# hhv-dcdarknet-varient-4.net
KiCad netlist of a schematic drawn in EAGLE
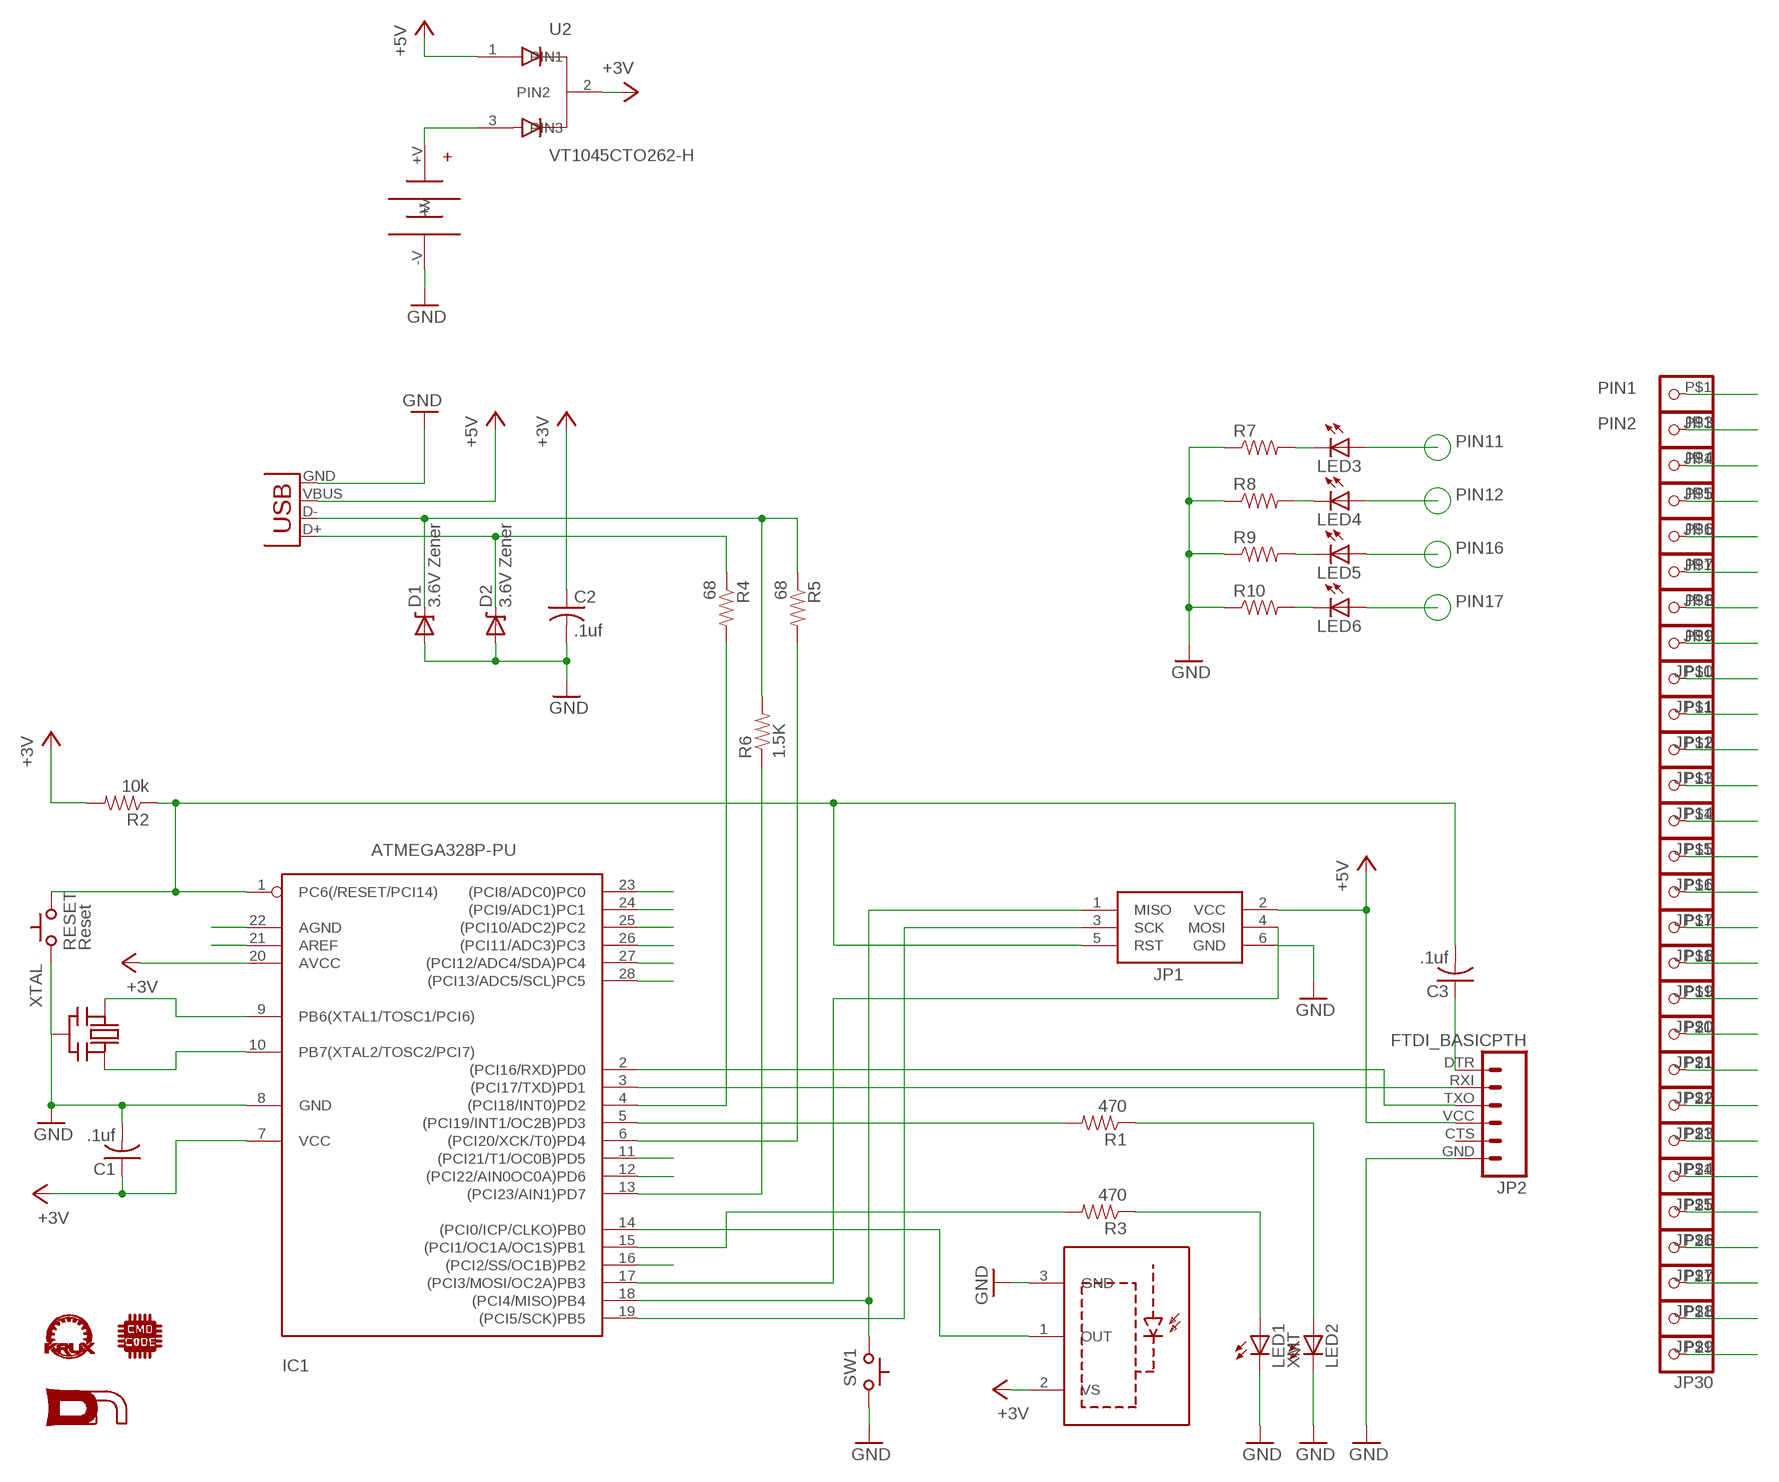
[diagram p0: schematic, sheet 1]

(export (version "E")
  (design (tool "Eeschema 10.0.6"))
  (components
    (comp (ref "C1")
      (value ".1uf")
      (footprint "eagle-import:C025-030X050")
      (libsource (lib "eagle-import") (part "C-US025-030X050"))
    )
    (comp (ref "C2")
      (value ".1uf")
      (footprint "eagle-import:C025-030X050")
      (libsource (lib "eagle-import") (part "C-US025-030X050"))
    )
    (comp (ref "C3")
      (value ".1uf")
      (footprint "eagle-import:C025-030X050")
      (libsource (lib "eagle-import") (part "C-US025-030X050"))
    )
    (comp (ref "D1")
      (value "3.6V Zener")
      (footprint "eagle-import:DIODE-ZENER")
      (libsource (lib "eagle-import") (part "DIODE-ZENERPTH"))
    )
    (comp (ref "D2")
      (value "3.6V Zener")
      (footprint "eagle-import:DIODE-ZENER")
      (libsource (lib "eagle-import") (part "DIODE-ZENERPTH"))
    )
    (comp (ref "IC1")
      (value "ATMEGA328P-PU")
      (footprint "eagle-import:DIL28-3")
      (libsource (lib "eagle-import") (part "ATMEGA168PV-10"))
    )
    (comp (ref "JP1")
      (value "JP1")
      (footprint "eagle-import:AVRISP")
      (libsource (lib "eagle-import") (part "AVRISP-6"))
    )
    (comp (ref "JP2")
      (value "FTDI_BASICPTH")
      (footprint "eagle-import:FTDI_BASIC")
      (libsource (lib "eagle-import") (part "FTDI_BASICPTH"))
    )
    (comp (ref "JP3")
      (value "PINHD-1X11X1_SQUARE")
      (footprint "eagle-import:1X1-SMALL_CUT")
      (libsource (lib "eagle-import") (part "PINHD-1X11X1_SQUARE"))
    )
    (comp (ref "JP4")
      (value "PINHD-1X11X1_SQUARE")
      (footprint "eagle-import:1X1-SMALL_CUT")
      (libsource (lib "eagle-import") (part "PINHD-1X11X1_SQUARE"))
    )
    (comp (ref "JP5")
      (value "PINHD-1X11X1_SQUARE")
      (footprint "eagle-import:1X1-SMALL_CUT")
      (libsource (lib "eagle-import") (part "PINHD-1X11X1_SQUARE"))
    )
    (comp (ref "JP6")
      (value "PINHD-1X11X1_SQUARE")
      (footprint "eagle-import:1X1-SMALL_CUT")
      (libsource (lib "eagle-import") (part "PINHD-1X11X1_SQUARE"))
    )
    (comp (ref "JP7")
      (value "PINHD-1X11X1_SQUARE")
      (footprint "eagle-import:1X1-SMALL_CUT")
      (libsource (lib "eagle-import") (part "PINHD-1X11X1_SQUARE"))
    )
    (comp (ref "JP8")
      (value "PINHD-1X11X1_SQUARE")
      (footprint "eagle-import:1X1-SMALL_CUT")
      (libsource (lib "eagle-import") (part "PINHD-1X11X1_SQUARE"))
    )
    (comp (ref "JP9")
      (value "PINHD-1X11X1_SQUARE")
      (footprint "eagle-import:1X1-SMALL_CUT")
      (libsource (lib "eagle-import") (part "PINHD-1X11X1_SQUARE"))
    )
    (comp (ref "JP10")
      (value "PINHD-1X11X1_SQUARE")
      (footprint "eagle-import:1X1-SMALL_CUT")
      (libsource (lib "eagle-import") (part "PINHD-1X11X1_SQUARE"))
    )
    (comp (ref "JP11")
      (value "PINHD-1X11X1_SQUARE")
      (footprint "eagle-import:1X1-SMALL_CUT")
      (libsource (lib "eagle-import") (part "PINHD-1X11X1_SQUARE"))
    )
    (comp (ref "JP12")
      (value "PINHD-1X11X1_SQUARE")
      (footprint "eagle-import:1X1-SMALL_CUT")
      (libsource (lib "eagle-import") (part "PINHD-1X11X1_SQUARE"))
    )
    (comp (ref "JP13")
      (value "PINHD-1X11X1_SQUARE")
      (footprint "eagle-import:1X1-SMALL_CUT")
      (libsource (lib "eagle-import") (part "PINHD-1X11X1_SQUARE"))
    )
    (comp (ref "JP14")
      (value "PINHD-1X11X1_SQUARE")
      (footprint "eagle-import:1X1-SMALL_CUT")
      (libsource (lib "eagle-import") (part "PINHD-1X11X1_SQUARE"))
    )
    (comp (ref "JP15")
      (value "PINHD-1X11X1_SQUARE")
      (footprint "eagle-import:1X1-SMALL_CUT")
      (libsource (lib "eagle-import") (part "PINHD-1X11X1_SQUARE"))
    )
    (comp (ref "JP16")
      (value "PINHD-1X11X1_SQUARE")
      (footprint "eagle-import:1X1-SMALL_CUT")
      (libsource (lib "eagle-import") (part "PINHD-1X11X1_SQUARE"))
    )
    (comp (ref "JP17")
      (value "PINHD-1X11X1_SQUARE")
      (footprint "eagle-import:1X1-SMALL_CUT")
      (libsource (lib "eagle-import") (part "PINHD-1X11X1_SQUARE"))
    )
    (comp (ref "JP18")
      (value "PINHD-1X11X1_SQUARE")
      (footprint "eagle-import:1X1-SMALL_CUT")
      (libsource (lib "eagle-import") (part "PINHD-1X11X1_SQUARE"))
    )
    (comp (ref "JP19")
      (value "PINHD-1X11X1_SQUARE")
      (footprint "eagle-import:1X1-SMALL_CUT")
      (libsource (lib "eagle-import") (part "PINHD-1X11X1_SQUARE"))
    )
    (comp (ref "JP20")
      (value "PINHD-1X11X1_SQUARE")
      (footprint "eagle-import:1X1-SMALL_CUT")
      (libsource (lib "eagle-import") (part "PINHD-1X11X1_SQUARE"))
    )
    (comp (ref "JP21")
      (value "PINHD-1X11X1_SQUARE")
      (footprint "eagle-import:1X1-SMALL_CUT")
      (libsource (lib "eagle-import") (part "PINHD-1X11X1_SQUARE"))
    )
    (comp (ref "JP22")
      (value "PINHD-1X11X1_SQUARE")
      (footprint "eagle-import:1X1-SMALL_CUT")
      (libsource (lib "eagle-import") (part "PINHD-1X11X1_SQUARE"))
    )
    (comp (ref "JP23")
      (value "PINHD-1X11X1_SQUARE")
      (footprint "eagle-import:1X1-SMALL_CUT")
      (libsource (lib "eagle-import") (part "PINHD-1X11X1_SQUARE"))
    )
    (comp (ref "JP24")
      (value "PINHD-1X11X1_SQUARE")
      (footprint "eagle-import:1X1-SMALL_CUT")
      (libsource (lib "eagle-import") (part "PINHD-1X11X1_SQUARE"))
    )
    (comp (ref "JP25")
      (value "PINHD-1X11X1_SQUARE")
      (footprint "eagle-import:1X1-SMALL_CUT")
      (libsource (lib "eagle-import") (part "PINHD-1X11X1_SQUARE"))
    )
    (comp (ref "JP26")
      (value "PINHD-1X11X1-SMALL")
      (footprint "eagle-import:1X1-SMALL")
      (libsource (lib "eagle-import") (part "PINHD-1X11X1-SMALL"))
    )
    (comp (ref "JP27")
      (value "PINHD-1X11X1_SQUARE")
      (footprint "eagle-import:1X1-SMALL_CUT")
      (libsource (lib "eagle-import") (part "PINHD-1X11X1_SQUARE"))
    )
    (comp (ref "JP28")
      (value "PINHD-1X11X1_SQUARE")
      (footprint "eagle-import:1X1-SMALL_CUT")
      (libsource (lib "eagle-import") (part "PINHD-1X11X1_SQUARE"))
    )
    (comp (ref "JP29")
      (value "PINHD-1X11X1_SQUARE")
      (footprint "eagle-import:1X1-SMALL_CUT")
      (libsource (lib "eagle-import") (part "PINHD-1X11X1_SQUARE"))
    )
    (comp (ref "JP30")
      (value "PINHD-1X11X1-SMALL")
      (footprint "eagle-import:1X1-SMALL")
      (libsource (lib "eagle-import") (part "PINHD-1X11X1-SMALL"))
    )
    (comp (ref "LED1")
      (value "XMT")
      (footprint "eagle-import:LED5MM-FLAT")
      (libsource (lib "eagle-import") (part "LED5MM-FLAT"))
    )
    (comp (ref "LED2")
      (value "LED5MM-FLAT")
      (footprint "eagle-import:LED5MM-FLAT")
      (libsource (lib "eagle-import") (part "LED5MM-FLAT"))
    )
    (comp (ref "LED3")
      (value "LED1206")
      (footprint "eagle-import:LED-1206")
      (libsource (lib "eagle-import") (part "SparkFun_LED1206"))
    )
    (comp (ref "LED4")
      (value "LED1206")
      (footprint "eagle-import:LED-1206")
      (libsource (lib "eagle-import") (part "SparkFun_LED1206"))
    )
    (comp (ref "LED5")
      (value "LED1206")
      (footprint "eagle-import:LED-1206")
      (libsource (lib "eagle-import") (part "SparkFun_LED1206"))
    )
    (comp (ref "LED6")
      (value "LED1206")
      (footprint "eagle-import:LED-1206")
      (libsource (lib "eagle-import") (part "SparkFun_LED1206"))
    )
    (comp (ref "R1")
      (value "470")
      (footprint "eagle-import:AXIAL-0.3")
      (libsource (lib "eagle-import") (part "RESISTORAXIAL-0.3"))
    )
    (comp (ref "R2")
      (value "10k")
      (footprint "eagle-import:AXIAL-0.3")
      (libsource (lib "eagle-import") (part "RESISTORAXIAL-0.3"))
    )
    (comp (ref "R3")
      (value "470")
      (footprint "eagle-import:AXIAL-0.3")
      (libsource (lib "eagle-import") (part "RESISTORAXIAL-0.3"))
    )
    (comp (ref "R4")
      (value "68")
      (footprint "eagle-import:AXIAL-0.3")
      (libsource (lib "eagle-import") (part "RESISTORAXIAL-0.3"))
    )
    (comp (ref "R5")
      (value "68")
      (footprint "eagle-import:AXIAL-0.3")
      (libsource (lib "eagle-import") (part "RESISTORAXIAL-0.3"))
    )
    (comp (ref "R6")
      (value "1.5K")
      (footprint "eagle-import:AXIAL-0.3")
      (libsource (lib "eagle-import") (part "RESISTORAXIAL-0.3"))
    )
    (comp (ref "R7")
      (value "RESISTOR1206")
      (footprint "eagle-import:1206")
      (libsource (lib "eagle-import") (part "SparkFun_RESISTOR1206"))
    )
    (comp (ref "R8")
      (value "RESISTOR1206")
      (footprint "eagle-import:1206")
      (libsource (lib "eagle-import") (part "SparkFun_RESISTOR1206"))
    )
    (comp (ref "R9")
      (value "RESISTOR1206")
      (footprint "eagle-import:1206")
      (libsource (lib "eagle-import") (part "SparkFun_RESISTOR1206"))
    )
    (comp (ref "R10")
      (value "RESISTOR1206")
      (footprint "eagle-import:1206")
      (libsource (lib "eagle-import") (part "SparkFun_RESISTOR1206"))
    )
    (comp (ref "RESET")
      (value "Reset")
      (footprint "eagle-import:TACTILE-2PIN")
      (libsource (lib "eagle-import") (part "SWITCH_TACTILETACTILE-2PIN"))
    )
    (comp (ref "SW1")
      (value "SWITCH_TACTILETACTILE-2PIN")
      (footprint "eagle-import:TACTILE-2PIN")
      (libsource (lib "eagle-import") (part "SWITCH_TACTILETACTILE-2PIN"))
    )
    (comp (ref "U$1")
      (value "DN_LOGO")
      (footprint "eagle-import:DN_LOGO")
      (libsource (lib "eagle-import") (part "DN_LOGO"))
    )
    (comp (ref "U$2")
      (value "CMDC0DE_LOGO")
      (footprint "eagle-import:CMDC0DE")
      (libsource (lib "eagle-import") (part "CMDC0DE_LOGO"))
    )
    (comp (ref "U$3")
      (value "KRUX_LOGO")
      (footprint "eagle-import:KRUX_LOGO")
      (libsource (lib "eagle-import") (part "KRUX_LOGO"))
    )
    (comp (ref "U$5")
      (value "12BH423-GR3-CELL_NOBORDER")
      (footprint "eagle-import:3-AAA-CELL_NOBORDER")
      (libsource (lib "eagle-import") (part "12BH423-GR3-CELL_NOBORDER"))
    )
    (comp (ref "U1")
      (value "RCV")
      (footprint "eagle-import:IR-MODULE")
      (libsource (lib "eagle-import") (part "SOP22"))
    )
    (comp (ref "U2")
      (value "VT1045CTO262-H")
      (footprint "eagle-import:TO262-H")
      (libsource (lib "eagle-import") (part "VT1045CTO262-H"))
    )
    (comp (ref "X2")
      (value "USB")
      (footprint "eagle-import:USB-B-PTH")
      (libsource (lib "eagle-import") (part "USBPTH"))
    )
    (comp (ref "XTAL")
      (value "CERMOSCILL-THM")
      (footprint "eagle-import:CERM_OSC")
      (libsource (lib "eagle-import") (part "CERMOSCILL-THM"))
    )
  )
  (nets
    (net (code "1") (name "+3V") (class "Default")
      (node (ref "C1") (pin "1") (pinfunction "1_1") (pintype "passive"))
      (node (ref "C2") (pin "1") (pinfunction "1_1") (pintype "passive"))
      (node (ref "IC1") (pin "20") (pinfunction "AVCC_20") (pintype "bidirectional"))
      (node (ref "IC1") (pin "7") (pinfunction "VCC_7") (pintype "bidirectional"))
      (node (ref "JP22") (pin "P$1") (pinfunction "1_P$1") (pintype "passive"))
      (node (ref "JP9") (pin "P$1") (pinfunction "1_P$1") (pintype "passive"))
      (node (ref "R2") (pin "P$2") (pinfunction "2_P$2") (pintype "passive"))
      (node (ref "U1") (pin "2") (pinfunction "VS_2") (pintype "bidirectional"))
      (node (ref "U2") (pin "2") (pinfunction "PIN2_2") (pintype "bidirectional"))
    )
    (net (code "2") (name "+5V") (class "Default")
      (node (ref "JP1") (pin "2") (pinfunction "VCC_2") (pintype "power_in"))
      (node (ref "JP2") (pin "VCC") (pinfunction "4_VCC") (pintype "passive"))
      (node (ref "U2") (pin "1") (pinfunction "PIN1_1") (pintype "bidirectional"))
      (node (ref "X2") (pin "VBUS") (pinfunction "VBUS_VBUS") (pintype "bidirectional"))
    )
    (net (code "3") (name "/PIN1") (class "Default")
      (node (ref "C3") (pin "2") (pinfunction "2_2") (pintype "passive"))
      (node (ref "IC1") (pin "1") (pinfunction "PC6(/RESET/PCI14)_1") (pintype "bidirectional"))
      (node (ref "JP1") (pin "5") (pinfunction "RST_5") (pintype "output"))
      (node (ref "JP3") (pin "P$1") (pinfunction "1_P$1") (pintype "passive"))
      (node (ref "R2") (pin "P$1") (pinfunction "1_P$1") (pintype "passive"))
      (node (ref "RESET") (pin "P$1") (pinfunction "A_P$1") (pintype "passive"))
    )
    (net (code "4") (name "/PIN2") (class "Default")
      (node (ref "IC1") (pin "2") (pinfunction "(PCI16/RXD)PD0_2") (pintype "bidirectional"))
      (node (ref "JP2") (pin "TXO") (pinfunction "3_TXO") (pintype "passive"))
      (node (ref "JP4") (pin "P$1") (pinfunction "1_P$1") (pintype "passive"))
    )
    (net (code "5") (name "/PIN3") (class "Default")
      (node (ref "IC1") (pin "3") (pinfunction "(PCI17/TXD)PD1_3") (pintype "bidirectional"))
      (node (ref "JP2") (pin "RXI") (pinfunction "2_RXI") (pintype "passive"))
      (node (ref "JP5") (pin "P$1") (pinfunction "1_P$1") (pintype "passive"))
    )
    (net (code "6") (name "/PIN4") (class "Default")
      (node (ref "IC1") (pin "4") (pinfunction "(PCI18/INT0)PD2_4") (pintype "bidirectional"))
      (node (ref "JP6") (pin "P$1") (pinfunction "1_P$1") (pintype "passive"))
      (node (ref "R4") (pin "P$2") (pinfunction "2_P$2") (pintype "passive"))
    )
    (net (code "7") (name "/PIN5") (class "Default")
      (node (ref "IC1") (pin "5") (pinfunction "(PCI19/INT1/OC2B)PD3_5") (pintype "bidirectional"))
      (node (ref "JP7") (pin "P$1") (pinfunction "1_P$1") (pintype "passive"))
      (node (ref "R1") (pin "P$2") (pinfunction "2_P$2") (pintype "passive"))
    )
    (net (code "8") (name "/PIN6") (class "Default")
      (node (ref "IC1") (pin "6") (pinfunction "(PCI20/XCK/T0)PD4_6") (pintype "bidirectional"))
      (node (ref "JP8") (pin "P$1") (pinfunction "1_P$1") (pintype "passive"))
      (node (ref "R5") (pin "P$2") (pinfunction "2_P$2") (pintype "passive"))
    )
    (net (code "9") (name "/PIN9") (class "Default")
      (node (ref "IC1") (pin "9") (pinfunction "PB6(XTAL1/TOSC1/PCI6)_9") (pintype "bidirectional"))
      (node (ref "JP11") (pin "P$1") (pinfunction "1_P$1") (pintype "passive"))
      (node (ref "XTAL") (pin "P$1") (pinfunction "IN_P$1") (pintype "bidirectional"))
    )
    (net (code "10") (name "/PIN10") (class "Default")
      (node (ref "IC1") (pin "10") (pinfunction "PB7(XTAL2/TOSC2/PCI7)_10") (pintype "bidirectional"))
      (node (ref "JP12") (pin "P$1") (pinfunction "1_P$1") (pintype "passive"))
      (node (ref "XTAL") (pin "P$3") (pinfunction "OUT_P$3") (pintype "bidirectional"))
    )
    (net (code "11") (name "/PIN11") (class "Default")
      (node (ref "IC1") (pin "11") (pinfunction "(PCI21/T1/OC0B)PD5_11") (pintype "bidirectional"))
      (node (ref "JP13") (pin "P$1") (pinfunction "1_P$1") (pintype "passive"))
      (node (ref "LED3") (pin "A") (pinfunction "A_A") (pintype "passive"))
    )
    (net (code "12") (name "/PIN12") (class "Default")
      (node (ref "IC1") (pin "12") (pinfunction "(PCI22/AIN0OC0A)PD6_12") (pintype "bidirectional"))
      (node (ref "JP14") (pin "P$1") (pinfunction "1_P$1") (pintype "passive"))
      (node (ref "LED4") (pin "A") (pinfunction "A_A") (pintype "passive"))
    )
    (net (code "13") (name "/PIN13") (class "Default")
      (node (ref "IC1") (pin "13") (pinfunction "(PCI23/AIN1)PD7_13") (pintype "bidirectional"))
      (node (ref "JP15") (pin "P$1") (pinfunction "1_P$1") (pintype "passive"))
      (node (ref "R6") (pin "P$1") (pinfunction "1_P$1") (pintype "passive"))
    )
    (net (code "14") (name "/PIN14") (class "Default")
      (node (ref "IC1") (pin "14") (pinfunction "(PCI0/ICP/CLKO)PB0_14") (pintype "bidirectional"))
      (node (ref "JP16") (pin "P$1") (pinfunction "1_P$1") (pintype "passive"))
      (node (ref "U1") (pin "1") (pinfunction "OUT_1") (pintype "bidirectional"))
    )
    (net (code "15") (name "/PIN15") (class "Default")
      (node (ref "IC1") (pin "15") (pinfunction "(PCI1/OC1A/OC1S)PB1_15") (pintype "bidirectional"))
      (node (ref "JP17") (pin "P$1") (pinfunction "1_P$1") (pintype "passive"))
      (node (ref "R3") (pin "P$2") (pinfunction "2_P$2") (pintype "passive"))
    )
    (net (code "16") (name "/PIN16") (class "Default")
      (node (ref "IC1") (pin "16") (pinfunction "(PCI2/SS/OC1B)PB2_16") (pintype "bidirectional"))
      (node (ref "JP18") (pin "P$1") (pinfunction "1_P$1") (pintype "passive"))
      (node (ref "LED5") (pin "A") (pinfunction "A_A") (pintype "passive"))
    )
    (net (code "17") (name "/PIN17") (class "Default")
      (node (ref "IC1") (pin "17") (pinfunction "(PCI3/MOSI/OC2A)PB3_17") (pintype "bidirectional"))
      (node (ref "JP1") (pin "4") (pinfunction "MOSI_4") (pintype "output"))
      (node (ref "JP19") (pin "P$1") (pinfunction "1_P$1") (pintype "passive"))
      (node (ref "LED6") (pin "A") (pinfunction "A_A") (pintype "passive"))
    )
    (net (code "18") (name "/PIN18") (class "Default")
      (node (ref "IC1") (pin "18") (pinfunction "(PCI4/MISO)PB4_18") (pintype "bidirectional"))
      (node (ref "JP1") (pin "1") (pinfunction "MISO_1") (pintype "input"))
      (node (ref "JP20") (pin "P$1") (pinfunction "1_P$1") (pintype "passive"))
      (node (ref "SW1") (pin "P$2") (pinfunction "C_P$2") (pintype "passive"))
    )
    (net (code "19") (name "/PIN19") (class "Default")
      (node (ref "IC1") (pin "19") (pinfunction "(PCI5/SCK)PB5_19") (pintype "bidirectional"))
      (node (ref "JP1") (pin "3") (pinfunction "SCK_3") (pintype "output"))
      (node (ref "JP21") (pin "P$1") (pinfunction "1_P$1") (pintype "passive"))
    )
    (net (code "20") (name "/PIN21") (class "Default")
      (node (ref "IC1") (pin "21") (pinfunction "AREF_21") (pintype "bidirectional"))
      (node (ref "JP23") (pin "P$1") (pinfunction "1_P$1") (pintype "passive"))
    )
    (net (code "21") (name "/PIN22") (class "Default")
      (node (ref "IC1") (pin "22") (pinfunction "AGND_22") (pintype "bidirectional"))
      (node (ref "JP24") (pin "P$1") (pinfunction "1_P$1") (pintype "passive"))
    )
    (net (code "22") (name "/PIN23") (class "Default")
      (node (ref "IC1") (pin "23") (pinfunction "(PCI8/ADC0)PC0_23") (pintype "bidirectional"))
      (node (ref "JP25") (pin "P$1") (pinfunction "1_P$1") (pintype "passive"))
    )
    (net (code "23") (name "/PIN24") (class "Default")
      (node (ref "IC1") (pin "24") (pinfunction "(PCI9/ADC1)PC1_24") (pintype "bidirectional"))
      (node (ref "JP26") (pin "P$1") (pinfunction "1_P$1") (pintype "passive"))
    )
    (net (code "24") (name "/PIN25") (class "Default")
      (node (ref "IC1") (pin "25") (pinfunction "(PCI10/ADC2)PC2_25") (pintype "bidirectional"))
      (node (ref "JP27") (pin "P$1") (pinfunction "1_P$1") (pintype "passive"))
    )
    (net (code "25") (name "/PIN26") (class "Default")
      (node (ref "IC1") (pin "26") (pinfunction "(PCI11/ADC3)PC3_26") (pintype "bidirectional"))
      (node (ref "JP28") (pin "P$1") (pinfunction "1_P$1") (pintype "passive"))
    )
    (net (code "26") (name "/PIN27") (class "Default")
      (node (ref "IC1") (pin "27") (pinfunction "(PCI12/ADC4/SDA)PC4_27") (pintype "bidirectional"))
      (node (ref "JP29") (pin "P$1") (pinfunction "1_P$1") (pintype "passive"))
    )
    (net (code "27") (name "/PIN28") (class "Default")
      (node (ref "IC1") (pin "28") (pinfunction "(PCI13/ADC5/SCL)PC5_28") (pintype "bidirectional"))
      (node (ref "JP30") (pin "P$1") (pinfunction "1_P$1") (pintype "passive"))
    )
    (net (code "28") (name "GND") (class "Default")
      (node (ref "C1") (pin "2") (pinfunction "2_2") (pintype "passive"))
      (node (ref "C2") (pin "2") (pinfunction "2_2") (pintype "passive"))
      (node (ref "D1") (pin "P$2") (pinfunction "A_P$2") (pintype "passive"))
      (node (ref "D2") (pin "P$2") (pinfunction "A_P$2") (pintype "passive"))
      (node (ref "IC1") (pin "8") (pinfunction "GND_8") (pintype "bidirectional"))
      (node (ref "JP1") (pin "6") (pinfunction "GND_6") (pintype "power_in"))
      (node (ref "JP10") (pin "P$1") (pinfunction "1_P$1") (pintype "passive"))
      (node (ref "JP2") (pin "GND") (pinfunction "6_GND") (pintype "passive"))
      (node (ref "LED1") (pin "K") (pinfunction "C_K") (pintype "passive"))
      (node (ref "LED2") (pin "K") (pinfunction "C_K") (pintype "passive"))
      (node (ref "R10") (pin "1") (pinfunction "1_1") (pintype "passive"))
      (node (ref "R7") (pin "1") (pinfunction "1_1") (pintype "passive"))
      (node (ref "R8") (pin "1") (pinfunction "1_1") (pintype "passive"))
      (node (ref "R9") (pin "1") (pinfunction "1_1") (pintype "passive"))
      (node (ref "RESET") (pin "P$2") (pinfunction "C_P$2") (pintype "passive"))
      (node (ref "SW1") (pin "P$1") (pinfunction "A_P$1") (pintype "passive"))
      (node (ref "U$5") (pin "-V") (pinfunction "-V_-V") (pintype "bidirectional"))
      (node (ref "U1") (pin "3") (pinfunction "GND_3") (pintype "bidirectional"))
      (node (ref "X2") (pin "GND") (pinfunction "GND_GND") (pintype "bidirectional"))
      (node (ref "XTAL") (pin "P$2") (pinfunction "GND_P$2") (pintype "bidirectional"))
    )
    (net (code "29") (name "Net-(D1-C)") (class "Default")
      (node (ref "D1") (pin "P$1") (pinfunction "C_P$1") (pintype "passive"))
      (node (ref "R5") (pin "P$1") (pinfunction "1_P$1") (pintype "passive"))
      (node (ref "R6") (pin "P$2") (pinfunction "2_P$2") (pintype "passive"))
      (node (ref "X2") (pin "D-") (pinfunction "D-_D-") (pintype "bidirectional"))
    )
    (net (code "30") (name "Net-(D2-C)") (class "Default")
      (node (ref "D2") (pin "P$1") (pinfunction "C_P$1") (pintype "passive"))
      (node (ref "R4") (pin "P$1") (pinfunction "1_P$1") (pintype "passive"))
      (node (ref "X2") (pin "D+") (pinfunction "D+_D+") (pintype "bidirectional"))
    )
    (net (code "31") (name "Net-(JP2-1)") (class "Default")
      (node (ref "C3") (pin "1") (pinfunction "1_1") (pintype "passive"))
      (node (ref "JP2") (pin "DTR") (pinfunction "1_DTR") (pintype "passive"))
    )
    (net (code "32") (name "Net-(LED3-PadC)") (class "Default")
      (node (ref "LED3") (pin "C") (pinfunction "C_C") (pintype "passive"))
      (node (ref "R7") (pin "2") (pinfunction "2_2") (pintype "passive"))
    )
    (net (code "33") (name "Net-(LED4-PadC)") (class "Default")
      (node (ref "LED4") (pin "C") (pinfunction "C_C") (pintype "passive"))
      (node (ref "R8") (pin "2") (pinfunction "2_2") (pintype "passive"))
    )
    (net (code "34") (name "Net-(LED5-PadC)") (class "Default")
      (node (ref "LED5") (pin "C") (pinfunction "C_C") (pintype "passive"))
      (node (ref "R9") (pin "2") (pinfunction "2_2") (pintype "passive"))
    )
    (net (code "35") (name "Net-(LED6-PadC)") (class "Default")
      (node (ref "LED6") (pin "C") (pinfunction "C_C") (pintype "passive"))
      (node (ref "R10") (pin "2") (pinfunction "2_2") (pintype "passive"))
    )
    (net (code "36") (name "Net-(R1-1)") (class "Default")
      (node (ref "LED2") (pin "A") (pinfunction "A_A") (pintype "passive"))
      (node (ref "R1") (pin "P$1") (pinfunction "1_P$1") (pintype "passive"))
    )
    (net (code "37") (name "Net-(R3-1)") (class "Default")
      (node (ref "LED1") (pin "A") (pinfunction "A_A") (pintype "passive"))
      (node (ref "R3") (pin "P$1") (pinfunction "1_P$1") (pintype "passive"))
    )
    (net (code "38") (name "Net-(U2-PIN3)") (class "Default")
      (node (ref "U$5") (pin "+V") (pinfunction "+V_+V") (pintype "bidirectional"))
      (node (ref "U2") (pin "3") (pinfunction "PIN3_3") (pintype "bidirectional"))
    )
    (net (code "39") (name "unconnected-(JP2-5-PadCTS)") (class "Default")
      (node (ref "JP2") (pin "CTS") (pinfunction "5_CTS") (pintype "passive"))
    )
  )
)
